# UI.net
KiCad netlist of a schematic drawn in Altium Designer
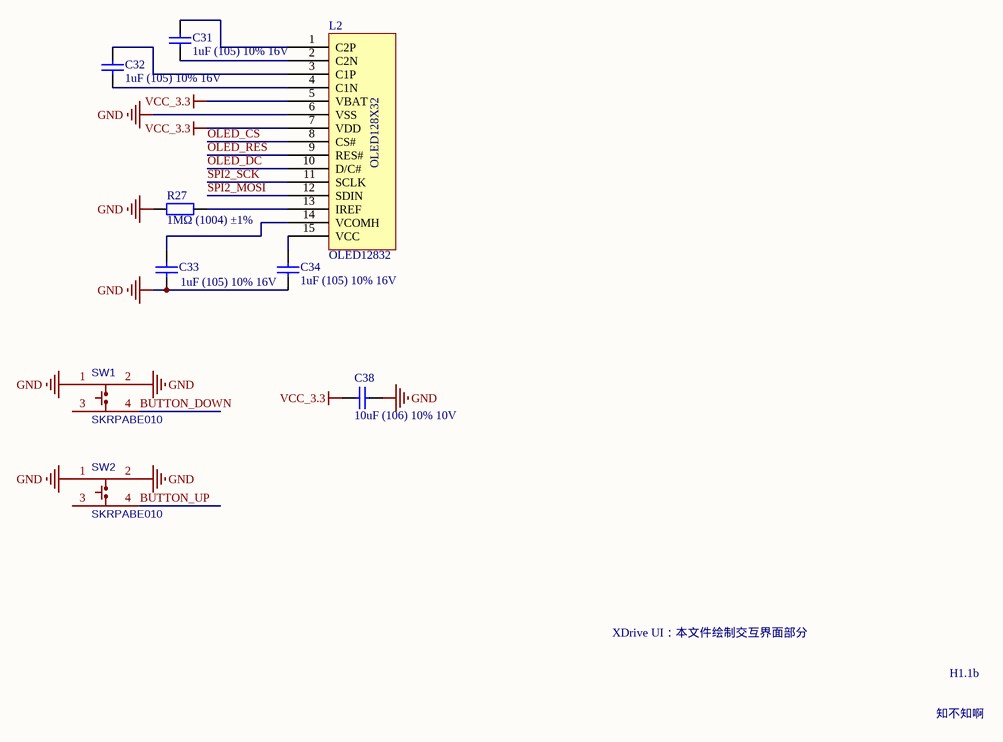
[diagram p0: UI.SchDoc]

(export (version "E")
  (design (tool "Eeschema 10.0.6"))
  (components
    (comp (ref "C31")
      (value "1uF (105) 10% 16V")
      (footprint "0603_C")
      (description "贴片电容")
      (libsource (lib "Miscellaneous Devices LC") (part "0603 1uF (105) 10% 50V"))
    )
    (comp (ref "C32")
      (value "1uF (105) 10% 16V")
      (footprint "0603_C")
      (description "贴片电容")
      (libsource (lib "Miscellaneous Devices LC") (part "0603 1uF (105) 10% 50V"))
    )
    (comp (ref "C33")
      (value "1uF (105) 10% 16V")
      (footprint "0603_C")
      (description "贴片电容")
      (libsource (lib "Miscellaneous Devices LC") (part "0603 1uF (105) 10% 50V"))
    )
    (comp (ref "C34")
      (value "1uF (105) 10% 16V")
      (footprint "0603_C")
      (description "贴片电容")
      (libsource (lib "Miscellaneous Devices LC") (part "0603 1uF (105) 10% 50V"))
    )
    (comp (ref "C38")
      (value "10uF (106) 10% 10V")
      (footprint "0603_C")
      (description "贴片电容")
      (libsource (lib "Miscellaneous Devices LC") (part "0603 10uF (106) 10% 10V"))
    )
    (comp (ref "L2")
      (value "OLED12832")
      (footprint "PCBComponent_1 - duplicate")
      (libsource (lib "OLED") (part "OLED12832"))
    )
    (comp (ref "R27")
      (value "1MΩ (1004) ±1%")
      (footprint "0603_R")
      (description "贴片电阻")
      (libsource (lib "Miscellaneous Devices LC") (part "0603 2MΩ (2004) 1%"))
    )
    (comp (ref "SW1")
      (value "SKRPABE010")
      (footprint "KEY-SMD-4P_L4.20-W3.20")
      (description "4脚贴片按键")
      (fields (field (name "BOM_SUPPLIER PART") "C115360"))
      (libsource (lib "杂库-按键") (part "SKRPABE010"))
    )
    (comp (ref "SW2")
      (value "SKRPABE010")
      (footprint "KEY-SMD-4P_L4.20-W3.20")
      (description "4脚贴片按键")
      (fields (field (name "BOM_SUPPLIER PART") "C115360"))
      (libsource (lib "杂库-按键") (part "SKRPABE010"))
    )
  )
  (nets
    (net (code "1") (name "/BUTTON_DOWN") (class "Default")
      (node (ref "SW1") (pin "4") (pinfunction "4_4") (pintype "passive"))
    )
    (net (code "2") (name "/BUTTON_UP") (class "Default")
      (node (ref "SW2") (pin "4") (pinfunction "4_4") (pintype "passive"))
    )
    (net (code "3") (name "/OLED_CS") (class "Default")
      (node (ref "L2") (pin "8") (pinfunction "CS#_8") (pintype "passive"))
    )
    (net (code "4") (name "/OLED_DC") (class "Default")
      (node (ref "L2") (pin "10") (pinfunction "D/C#_10") (pintype "passive"))
    )
    (net (code "5") (name "/OLED_RES") (class "Default")
      (node (ref "L2") (pin "9") (pinfunction "RES#_9") (pintype "passive"))
    )
    (net (code "6") (name "/SPI2_MOSI") (class "Default")
      (node (ref "L2") (pin "12") (pinfunction "SDIN_12") (pintype "passive"))
    )
    (net (code "7") (name "/SPI2_SCK") (class "Default")
      (node (ref "L2") (pin "11") (pinfunction "SCLK_11") (pintype "passive"))
    )
    (net (code "8") (name "GND") (class "Default")
      (node (ref "C33") (pin "1") (pinfunction "1_1") (pintype "passive"))
      (node (ref "C34") (pin "1") (pinfunction "1_1") (pintype "passive"))
      (node (ref "C38") (pin "1") (pinfunction "1_1") (pintype "passive"))
      (node (ref "L2") (pin "6") (pinfunction "VSS_6") (pintype "passive"))
      (node (ref "R27") (pin "1") (pinfunction "1_1") (pintype "passive"))
      (node (ref "SW1") (pin "1") (pinfunction "1_1") (pintype "passive"))
      (node (ref "SW1") (pin "2") (pinfunction "2_2") (pintype "passive"))
      (node (ref "SW2") (pin "1") (pinfunction "1_1") (pintype "passive"))
      (node (ref "SW2") (pin "2") (pinfunction "2_2") (pintype "passive"))
    )
    (net (code "9") (name "Net-(L2-C1N)") (class "Default")
      (node (ref "C32") (pin "1") (pinfunction "1_1") (pintype "passive"))
      (node (ref "L2") (pin "4") (pinfunction "C1N_4") (pintype "passive"))
    )
    (net (code "10") (name "Net-(L2-C1P)") (class "Default")
      (node (ref "C32") (pin "2") (pinfunction "2_2") (pintype "passive"))
      (node (ref "L2") (pin "3") (pinfunction "C1P_3") (pintype "passive"))
    )
    (net (code "11") (name "Net-(L2-C2N)") (class "Default")
      (node (ref "C31") (pin "1") (pinfunction "1_1") (pintype "passive"))
      (node (ref "L2") (pin "2") (pinfunction "C2N_2") (pintype "passive"))
    )
    (net (code "12") (name "Net-(L2-C2P)") (class "Default")
      (node (ref "C31") (pin "2") (pinfunction "2_2") (pintype "passive"))
      (node (ref "L2") (pin "1") (pinfunction "C2P_1") (pintype "passive"))
    )
    (net (code "13") (name "Net-(L2-IREF)") (class "Default")
      (node (ref "L2") (pin "13") (pinfunction "IREF_13") (pintype "passive"))
      (node (ref "R27") (pin "2") (pinfunction "2_2") (pintype "passive"))
    )
    (net (code "14") (name "Net-(L2-VCC)") (class "Default")
      (node (ref "C34") (pin "2") (pinfunction "2_2") (pintype "passive"))
      (node (ref "L2") (pin "15") (pinfunction "VCC_15") (pintype "passive"))
    )
    (net (code "15") (name "Net-(L2-VCOMH)") (class "Default")
      (node (ref "C33") (pin "2") (pinfunction "2_2") (pintype "passive"))
      (node (ref "L2") (pin "14") (pinfunction "VCOMH_14") (pintype "passive"))
    )
    (net (code "16") (name "VCC_3.3") (class "Default")
      (node (ref "C38") (pin "2") (pinfunction "2_2") (pintype "passive"))
      (node (ref "L2") (pin "5") (pinfunction "VBAT_5") (pintype "passive"))
      (node (ref "L2") (pin "7") (pinfunction "VDD_7") (pintype "passive"))
    )
    (net (code "17") (name "unconnected-(SW1-Pad3)") (class "Default")
      (node (ref "SW1") (pin "3") (pinfunction "3_3") (pintype "passive"))
    )
    (net (code "18") (name "unconnected-(SW2-Pad3)") (class "Default")
      (node (ref "SW2") (pin "3") (pinfunction "3_3") (pintype "passive"))
    )
  )
)
